# cSLIM_nRF9160.net
KiCad netlist of a schematic drawn in Altium Designer
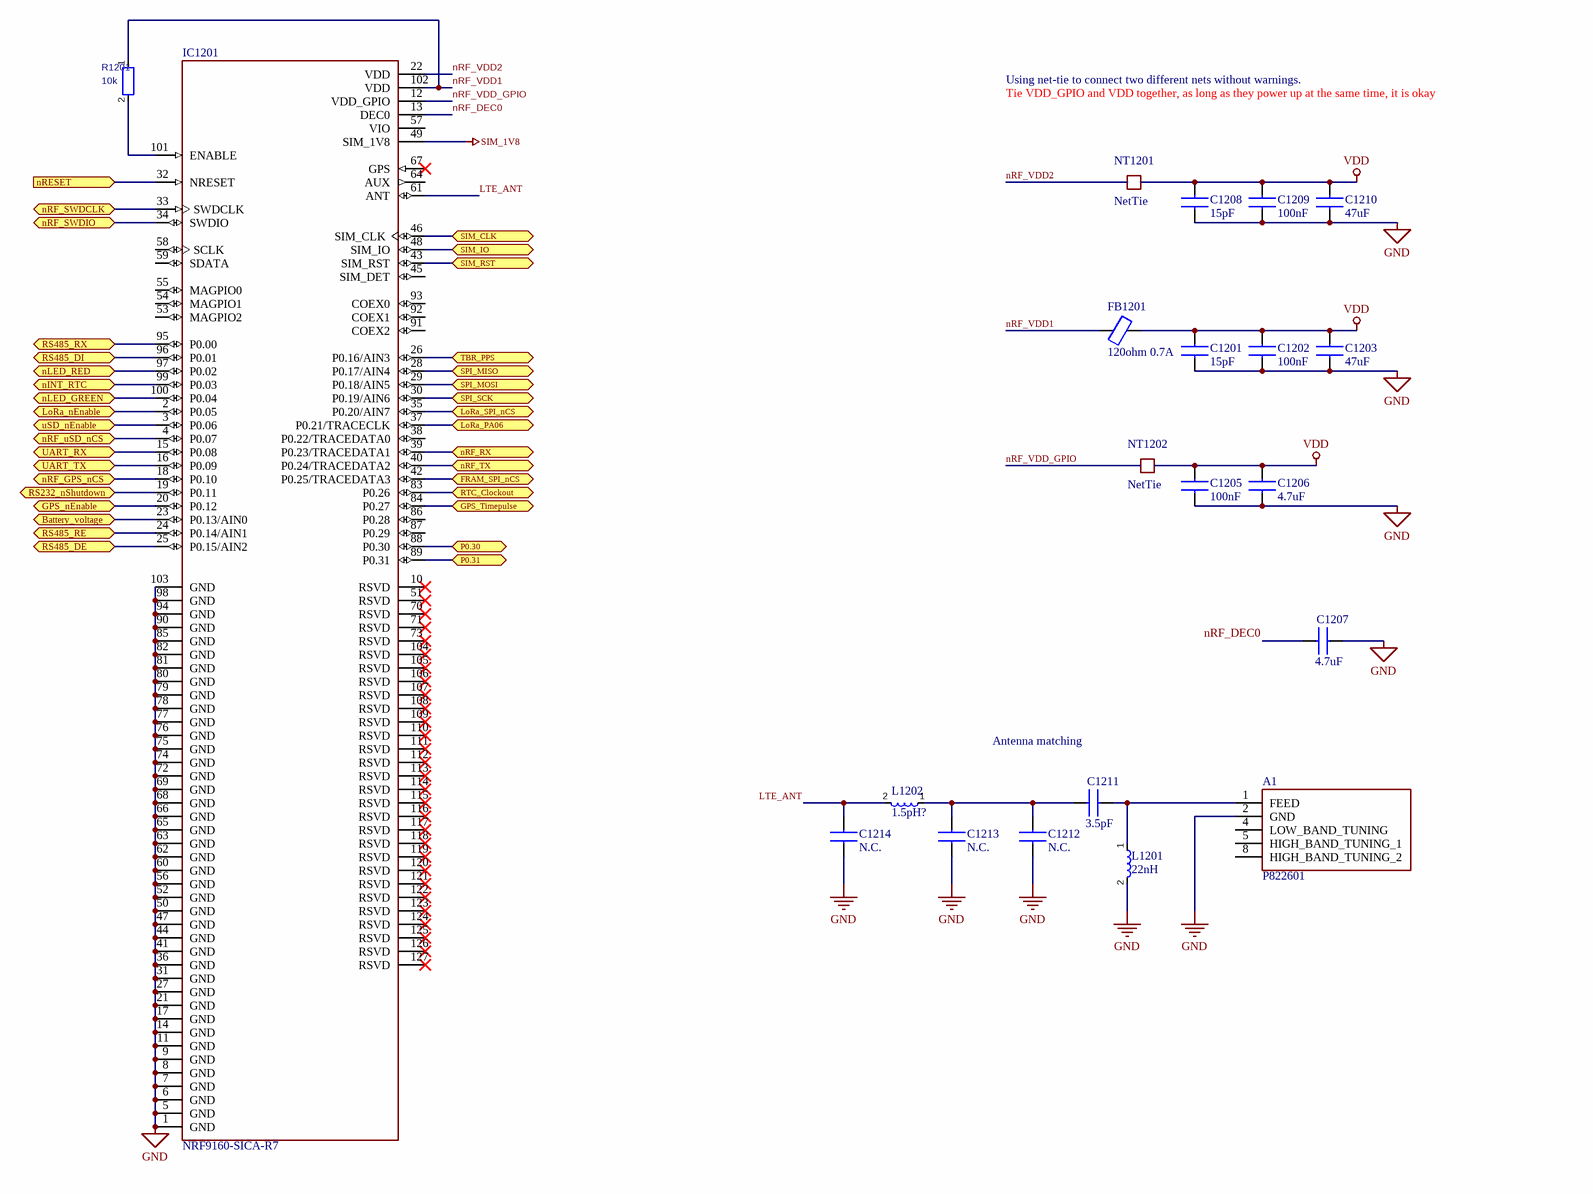
[diagram p0: cSLIM_nRF9160.SchDoc]

(export (version "E")
  (design (tool "Eeschema 10.0.6"))
  (components
    (comp (ref "A1")
      (value "P822601")
      (footprint "cSLIM-SA:P822601")
      (description "Antenna")
      (fields (field (name "MOUSER PART NUMBER") "581-P822601"))
      (libsource (lib "cSLIM-SA") (part "P822601"))
    )
    (comp (ref "C1201")
      (value "15pF")
      (footprint "cSLIM-SA:CAPC1608X90N")
      (description "Capacitor")
      (fields
        (field (name "MANUFACTURER_PART_NUMBER") "06033G104ZAT2A")
        (field (name "MOUSER PART NUMBER") "581-06033G104Z")
      )
      (libsource (lib "cSLIM-SA") (part "C"))
    )
    (comp (ref "C1202")
      (value "100nF")
      (footprint "cSLIM-SA:CAPC1608X90N")
      (description "Capacitor")
      (fields
        (field (name "MANUFACTURER_PART_NUMBER") "06033G104ZAT2A")
        (field (name "MOUSER PART NUMBER") "581-06033G104Z")
      )
      (libsource (lib "cSLIM-SA") (part "C"))
    )
    (comp (ref "C1203")
      (value "47uF")
      (footprint "cSLIM-SA:CAPC1608X90N")
      (description "Capacitor")
      (fields
        (field (name "MANUFACTURER_PART_NUMBER") "06033G104ZAT2A")
        (field (name "MOUSER PART NUMBER") "581-06033G104Z")
      )
      (libsource (lib "cSLIM-SA") (part "C"))
    )
    (comp (ref "C1205")
      (value "100nF")
      (footprint "cSLIM-SA:CAPC1608X90N")
      (description "Capacitor")
      (fields
        (field (name "MANUFACTURER_PART_NUMBER") "06033G104ZAT2A")
        (field (name "MOUSER PART NUMBER") "581-06033G104Z")
      )
      (libsource (lib "cSLIM-SA") (part "C"))
    )
    (comp (ref "C1206")
      (value "4.7uF")
      (footprint "cSLIM-SA:CAPC1608X90N")
      (description "Capacitor")
      (fields
        (field (name "MANUFACTURER_PART_NUMBER") "06033G104ZAT2A")
        (field (name "MOUSER PART NUMBER") "581-06033G104Z")
      )
      (libsource (lib "cSLIM-SA") (part "C"))
    )
    (comp (ref "C1207")
      (value "4.7uF")
      (footprint "cSLIM-SA:CAPC1608X90N")
      (description "Capacitor")
      (fields
        (field (name "MANUFACTURER_PART_NUMBER") "06033G104ZAT2A")
        (field (name "MOUSER PART NUMBER") "581-06033G104Z")
      )
      (libsource (lib "cSLIM-SA") (part "C"))
    )
    (comp (ref "C1208")
      (value "15pF")
      (footprint "cSLIM-SA:CAPC1608X90N")
      (description "Capacitor")
      (fields
        (field (name "MANUFACTURER_PART_NUMBER") "06033G104ZAT2A")
        (field (name "MOUSER PART NUMBER") "581-06033G104Z")
      )
      (libsource (lib "cSLIM-SA") (part "C"))
    )
    (comp (ref "C1209")
      (value "100nF")
      (footprint "cSLIM-SA:CAPC1608X90N")
      (description "Capacitor")
      (fields
        (field (name "MANUFACTURER_PART_NUMBER") "06033G104ZAT2A")
        (field (name "MOUSER PART NUMBER") "581-06033G104Z")
      )
      (libsource (lib "cSLIM-SA") (part "C"))
    )
    (comp (ref "C1210")
      (value "47uF")
      (footprint "cSLIM-SA:CAPC1608X90N")
      (description "Capacitor")
      (fields
        (field (name "MANUFACTURER_PART_NUMBER") "06033G104ZAT2A")
        (field (name "MOUSER PART NUMBER") "581-06033G104Z")
      )
      (libsource (lib "cSLIM-SA") (part "C"))
    )
    (comp (ref "C1211")
      (value "3.5pF")
      (footprint "cSLIM-SA:CAPC1608X90N")
      (description "Capacitor")
      (fields
        (field (name "MANUFACTURER_PART_NUMBER") "06033G104ZAT2A")
        (field (name "MOUSER PART NUMBER") "581-06033G104Z")
      )
      (libsource (lib "cSLIM-SA") (part "C"))
    )
    (comp (ref "C1212")
      (value "N.C.")
      (footprint "cSLIM-SA:CAPC1608X90N")
      (description "Capacitor")
      (fields
        (field (name "MANUFACTURER_PART_NUMBER") "06033G104ZAT2A")
        (field (name "MOUSER PART NUMBER") "581-06033G104Z")
      )
      (libsource (lib "cSLIM-SA") (part "C"))
    )
    (comp (ref "C1213")
      (value "N.C.")
      (footprint "cSLIM-SA:CAPC1608X90N")
      (description "Capacitor")
      (fields
        (field (name "MANUFACTURER_PART_NUMBER") "06033G104ZAT2A")
        (field (name "MOUSER PART NUMBER") "581-06033G104Z")
      )
      (libsource (lib "cSLIM-SA") (part "C"))
    )
    (comp (ref "C1214")
      (value "N.C.")
      (footprint "cSLIM-SA:CAPC1608X90N")
      (description "Capacitor")
      (fields
        (field (name "MANUFACTURER_PART_NUMBER") "06033G104ZAT2A")
        (field (name "MOUSER PART NUMBER") "581-06033G104Z")
      )
      (libsource (lib "cSLIM-SA") (part "C"))
    )
    (comp (ref "FB1201")
      (value "120ohm 0.7A")
      (footprint "CAPC1608X90N")
      (libsource (lib "cSLIM-SA") (part "Ferrite_Bead"))
    )
    (comp (ref "IC1201")
      (value "NRF9160-SICA-R7")
      (footprint "cSLIM-SA:XCVR_NRF9160-SICA-R7")
      (description "IC RF TxRx + MCU Cellular GPS 700MHz ~ 2.2GHz 161-TFLGA Module")
      (fields (field (name "MF") "Nordic Semiconductor ASA"))
      (libsource (lib "cSLIM-SA") (part "NRF9160-SICA-R7"))
    )
    (comp (ref "L1201") (value "22nH") (footprint "L-1608") (libsource (lib "cSLIM-SA") (part "L")))
    (comp (ref "L1202") (value "1.5pH?") (footprint "L-1608") (libsource (lib "cSLIM-SA") (part "L")))
    (comp (ref "NT1201")
      (value "NetTie")
      (footprint "NETTIE_FP")
      (libsource (lib "cSLIM-SA") (part "NetTie"))
    )
    (comp (ref "NT1202")
      (value "NetTie")
      (footprint "NETTIE_FP")
      (libsource (lib "cSLIM-SA") (part "NetTie"))
    )
    (comp (ref "R1201") (value "10k") (footprint "RESC1608X55N") (libsource (lib "cSLIM-SA") (part "R")))
  )
  (nets
    (net (code "1") (name "/Battery_voltage") (class "Default")
      (node (ref "IC1201") (pin "23") (pinfunction "P0.13/AIN0_23") (pintype "bidirectional"))
    )
    (net (code "2") (name "/FRAM_SPI_nCS") (class "Default")
      (node (ref "IC1201") (pin "42") (pinfunction "P0.25/TRACEDATA3_42") (pintype "bidirectional"))
    )
    (net (code "3") (name "/GPS_Timepulse") (class "Default")
      (node (ref "IC1201") (pin "84") (pinfunction "P0.27_84") (pintype "bidirectional"))
    )
    (net (code "4") (name "/GPS_nEnable") (class "Default")
      (node (ref "IC1201") (pin "20") (pinfunction "P0.12_20") (pintype "bidirectional"))
    )
    (net (code "5") (name "/LTE_ANT") (class "Default")
      (node (ref "C1214") (pin "1") (pinfunction "1_1") (pintype "passive"))
      (node (ref "IC1201") (pin "61") (pinfunction "ANT_61") (pintype "bidirectional"))
      (node (ref "L1202") (pin "2") (pinfunction "2_2") (pintype "passive"))
    )
    (net (code "6") (name "/LoRa_PA06") (class "Default")
      (node (ref "IC1201") (pin "37") (pinfunction "P0.21/TRACECLK_37") (pintype "bidirectional"))
    )
    (net (code "7") (name "/LoRa_SPI_nCS") (class "Default")
      (node (ref "IC1201") (pin "35") (pinfunction "P0.20/AIN7_35") (pintype "bidirectional"))
    )
    (net (code "8") (name "/LoRa_nEnable") (class "Default")
      (node (ref "IC1201") (pin "2") (pinfunction "P0.05_2") (pintype "bidirectional"))
    )
    (net (code "9") (name "/P0.30") (class "Default")
      (node (ref "IC1201") (pin "88") (pinfunction "P0.30_88") (pintype "bidirectional"))
    )
    (net (code "10") (name "/P0.31") (class "Default")
      (node (ref "IC1201") (pin "89") (pinfunction "P0.31_89") (pintype "bidirectional"))
    )
    (net (code "11") (name "/RS232_nShutdown") (class "Default")
      (node (ref "IC1201") (pin "19") (pinfunction "P0.11_19") (pintype "bidirectional"))
    )
    (net (code "12") (name "/RS485_DE") (class "Default")
      (node (ref "IC1201") (pin "25") (pinfunction "P0.15/AIN2_25") (pintype "bidirectional"))
    )
    (net (code "13") (name "/RS485_DI") (class "Default")
      (node (ref "IC1201") (pin "96") (pinfunction "P0.01_96") (pintype "bidirectional"))
    )
    (net (code "14") (name "/RS485_RE") (class "Default")
      (node (ref "IC1201") (pin "24") (pinfunction "P0.14/AIN1_24") (pintype "bidirectional"))
    )
    (net (code "15") (name "/RS485_RX") (class "Default")
      (node (ref "IC1201") (pin "95") (pinfunction "P0.00_95") (pintype "bidirectional"))
    )
    (net (code "16") (name "/RTC_Clockout") (class "Default")
      (node (ref "IC1201") (pin "83") (pinfunction "P0.26_83") (pintype "bidirectional"))
    )
    (net (code "17") (name "/SIM_CLK") (class "Default")
      (node (ref "IC1201") (pin "46") (pinfunction "SIM_CLK_46") (pintype "bidirectional"))
    )
    (net (code "18") (name "/SIM_IO") (class "Default")
      (node (ref "IC1201") (pin "48") (pinfunction "SIM_IO_48") (pintype "bidirectional"))
    )
    (net (code "19") (name "/SIM_RST") (class "Default")
      (node (ref "IC1201") (pin "43") (pinfunction "SIM_RST_43") (pintype "bidirectional"))
    )
    (net (code "20") (name "/SPI_MISO") (class "Default")
      (node (ref "IC1201") (pin "28") (pinfunction "P0.17/AIN4_28") (pintype "bidirectional"))
    )
    (net (code "21") (name "/SPI_MOSI") (class "Default")
      (node (ref "IC1201") (pin "29") (pinfunction "P0.18/AIN5_29") (pintype "bidirectional"))
    )
    (net (code "22") (name "/SPI_SCK") (class "Default")
      (node (ref "IC1201") (pin "30") (pinfunction "P0.19/AIN6_30") (pintype "bidirectional"))
    )
    (net (code "23") (name "/TBR_PPS") (class "Default")
      (node (ref "IC1201") (pin "26") (pinfunction "P0.16/AIN3_26") (pintype "bidirectional"))
    )
    (net (code "24") (name "/UART_RX") (class "Default")
      (node (ref "IC1201") (pin "15") (pinfunction "P0.08_15") (pintype "bidirectional"))
    )
    (net (code "25") (name "/UART_TX") (class "Default")
      (node (ref "IC1201") (pin "16") (pinfunction "P0.09_16") (pintype "bidirectional"))
    )
    (net (code "26") (name "/nINT_RTC") (class "Default")
      (node (ref "IC1201") (pin "99") (pinfunction "P0.03_99") (pintype "bidirectional"))
    )
    (net (code "27") (name "/nLED_GREEN") (class "Default")
      (node (ref "IC1201") (pin "100") (pinfunction "P0.04_100") (pintype "bidirectional"))
    )
    (net (code "28") (name "/nLED_RED") (class "Default")
      (node (ref "IC1201") (pin "97") (pinfunction "P0.02_97") (pintype "bidirectional"))
    )
    (net (code "29") (name "/nRESET") (class "Default")
      (node (ref "IC1201") (pin "32") (pinfunction "NRESET_32") (pintype "input"))
    )
    (net (code "30") (name "/nRF_DEC0") (class "Default")
      (node (ref "C1207") (pin "1") (pinfunction "1_1") (pintype "passive"))
      (node (ref "IC1201") (pin "13") (pinfunction "DEC0_13") (pintype "power_in"))
    )
    (net (code "31") (name "/nRF_GPS_nCS") (class "Default")
      (node (ref "IC1201") (pin "18") (pinfunction "P0.10_18") (pintype "bidirectional"))
    )
    (net (code "32") (name "/nRF_RX") (class "Default")
      (node (ref "IC1201") (pin "39") (pinfunction "P0.23/TRACEDATA1_39") (pintype "bidirectional"))
    )
    (net (code "33") (name "/nRF_SWDCLK") (class "Default")
      (node (ref "IC1201") (pin "33") (pinfunction "SWDCLK_33") (pintype "input"))
    )
    (net (code "34") (name "/nRF_SWDIO") (class "Default")
      (node (ref "IC1201") (pin "34") (pinfunction "SWDIO_34") (pintype "bidirectional"))
    )
    (net (code "35") (name "/nRF_TX") (class "Default")
      (node (ref "IC1201") (pin "40") (pinfunction "P0.24/TRACEDATA2_40") (pintype "bidirectional"))
    )
    (net (code "36") (name "/nRF_VDD1") (class "Default")
      (node (ref "FB1201") (pin "1") (pinfunction "1_1") (pintype "passive"))
      (node (ref "IC1201") (pin "102") (pinfunction "VDD_102") (pintype "power_in"))
      (node (ref "R1201") (pin "1") (pinfunction "1_1") (pintype "passive"))
    )
    (net (code "37") (name "/nRF_VDD2") (class "Default")
      (node (ref "IC1201") (pin "22") (pinfunction "VDD_22") (pintype "power_in"))
      (node (ref "NT1201") (pin "1") (pintype "passive"))
    )
    (net (code "38") (name "/nRF_VDD_GPIO") (class "Default")
      (node (ref "IC1201") (pin "12") (pinfunction "VDD_GPIO_12") (pintype "power_in"))
      (node (ref "NT1202") (pin "1") (pintype "passive"))
    )
    (net (code "39") (name "/nRF_uSD_nCS") (class "Default")
      (node (ref "IC1201") (pin "4") (pinfunction "P0.07_4") (pintype "bidirectional"))
    )
    (net (code "40") (name "/uSD_nEnable") (class "Default")
      (node (ref "IC1201") (pin "3") (pinfunction "P0.06_3") (pintype "bidirectional"))
    )
    (net (code "41") (name "GND") (class "Default")
      (node (ref "A1") (pin "2") (pinfunction "GND_2") (pintype "passive"))
      (node (ref "C1201") (pin "2") (pinfunction "2_2") (pintype "passive"))
      (node (ref "C1202") (pin "2") (pinfunction "2_2") (pintype "passive"))
      (node (ref "C1203") (pin "2") (pinfunction "2_2") (pintype "passive"))
      (node (ref "C1205") (pin "2") (pinfunction "2_2") (pintype "passive"))
      (node (ref "C1206") (pin "2") (pinfunction "2_2") (pintype "passive"))
      (node (ref "C1207") (pin "2") (pinfunction "2_2") (pintype "passive"))
      (node (ref "C1208") (pin "2") (pinfunction "2_2") (pintype "passive"))
      (node (ref "C1209") (pin "2") (pinfunction "2_2") (pintype "passive"))
      (node (ref "C1210") (pin "2") (pinfunction "2_2") (pintype "passive"))
      (node (ref "C1212") (pin "2") (pinfunction "2_2") (pintype "passive"))
      (node (ref "C1213") (pin "2") (pinfunction "2_2") (pintype "passive"))
      (node (ref "C1214") (pin "2") (pinfunction "2_2") (pintype "passive"))
      (node (ref "IC1201") (pin "1") (pinfunction "GND_1") (pintype "power_in"))
      (node (ref "IC1201") (pin "103") (pinfunction "GND_103") (pintype "power_in"))
      (node (ref "IC1201") (pin "11") (pinfunction "GND_11") (pintype "passive"))
      (node (ref "IC1201") (pin "14") (pinfunction "GND_14") (pintype "power_in"))
      (node (ref "IC1201") (pin "17") (pinfunction "GND_17") (pintype "power_in"))
      (node (ref "IC1201") (pin "21") (pinfunction "GND_21") (pintype "power_in"))
      (node (ref "IC1201") (pin "27") (pinfunction "GND_27") (pintype "power_in"))
      (node (ref "IC1201") (pin "31") (pinfunction "GND_31") (pintype "power_in"))
      (node (ref "IC1201") (pin "36") (pinfunction "GND_36") (pintype "power_in"))
      (node (ref "IC1201") (pin "41") (pinfunction "GND_41") (pintype "power_in"))
      (node (ref "IC1201") (pin "44") (pinfunction "GND_44") (pintype "power_in"))
      (node (ref "IC1201") (pin "47") (pinfunction "GND_47") (pintype "power_in"))
      (node (ref "IC1201") (pin "5") (pinfunction "GND_5") (pintype "power_in"))
      (node (ref "IC1201") (pin "50") (pinfunction "GND_50") (pintype "power_in"))
      (node (ref "IC1201") (pin "52") (pinfunction "GND_52") (pintype "power_in"))
      (node (ref "IC1201") (pin "56") (pinfunction "GND_56") (pintype "power_in"))
      (node (ref "IC1201") (pin "6") (pinfunction "GND_6") (pintype "passive"))
      (node (ref "IC1201") (pin "60") (pinfunction "GND_60") (pintype "power_in"))
      (node (ref "IC1201") (pin "62") (pinfunction "GND_62") (pintype "power_in"))
      (node (ref "IC1201") (pin "63") (pinfunction "GND_63") (pintype "power_in"))
      (node (ref "IC1201") (pin "65") (pinfunction "GND_65") (pintype "power_in"))
      (node (ref "IC1201") (pin "66") (pinfunction "GND_66") (pintype "power_in"))
      (node (ref "IC1201") (pin "68") (pinfunction "GND_68") (pintype "passive"))
      (node (ref "IC1201") (pin "69") (pinfunction "GND_69") (pintype "passive"))
      (node (ref "IC1201") (pin "7") (pinfunction "GND_7") (pintype "passive"))
      (node (ref "IC1201") (pin "72") (pinfunction "GND_72") (pintype "power_in"))
      (node (ref "IC1201") (pin "74") (pinfunction "GND_74") (pintype "power_in"))
      (node (ref "IC1201") (pin "75") (pinfunction "GND_75") (pintype "power_in"))
      (node (ref "IC1201") (pin "76") (pinfunction "GND_76") (pintype "power_in"))
      (node (ref "IC1201") (pin "77") (pinfunction "GND_77") (pintype "power_in"))
      (node (ref "IC1201") (pin "78") (pinfunction "GND_78") (pintype "power_in"))
      (node (ref "IC1201") (pin "79") (pinfunction "GND_79") (pintype "power_in"))
      (node (ref "IC1201") (pin "8") (pinfunction "GND_8") (pintype "passive"))
      (node (ref "IC1201") (pin "80") (pinfunction "GND_80") (pintype "power_in"))
      (node (ref "IC1201") (pin "81") (pinfunction "GND_81") (pintype "power_in"))
      (node (ref "IC1201") (pin "82") (pinfunction "GND_82") (pintype "power_in"))
      (node (ref "IC1201") (pin "85") (pinfunction "GND_85") (pintype "power_in"))
      (node (ref "IC1201") (pin "9") (pinfunction "GND_9") (pintype "power_in"))
      (node (ref "IC1201") (pin "90") (pinfunction "GND_90") (pintype "power_in"))
      (node (ref "IC1201") (pin "94") (pinfunction "GND_94") (pintype "power_in"))
      (node (ref "IC1201") (pin "98") (pinfunction "GND_98") (pintype "power_in"))
      (node (ref "L1201") (pin "2") (pinfunction "2_2") (pintype "passive"))
    )
    (net (code "42") (name "Net-(A1-FEED)") (class "Default")
      (node (ref "A1") (pin "1") (pinfunction "FEED_1") (pintype "passive"))
      (node (ref "C1211") (pin "2") (pinfunction "2_2") (pintype "passive"))
      (node (ref "L1201") (pin "1") (pinfunction "1_1") (pintype "passive"))
    )
    (net (code "43") (name "Net-(C1211-Pad1)") (class "Default")
      (node (ref "C1211") (pin "1") (pinfunction "1_1") (pintype "passive"))
      (node (ref "C1212") (pin "1") (pinfunction "1_1") (pintype "passive"))
      (node (ref "C1213") (pin "1") (pinfunction "1_1") (pintype "passive"))
      (node (ref "L1202") (pin "1") (pinfunction "1_1") (pintype "passive"))
    )
    (net (code "44") (name "Net-(IC1201-ENABLE)") (class "Default")
      (node (ref "IC1201") (pin "101") (pinfunction "ENABLE_101") (pintype "input"))
      (node (ref "R1201") (pin "2") (pinfunction "2_2") (pintype "passive"))
    )
    (net (code "45") (name "SIM_1V8") (class "Default")
      (node (ref "IC1201") (pin "49") (pinfunction "SIM_1V8_49") (pintype "power_in"))
    )
    (net (code "46") (name "VDD") (class "Default")
      (node (ref "C1201") (pin "1") (pinfunction "1_1") (pintype "passive"))
      (node (ref "C1202") (pin "1") (pinfunction "1_1") (pintype "passive"))
      (node (ref "C1203") (pin "1") (pinfunction "1_1") (pintype "passive"))
      (node (ref "C1205") (pin "1") (pinfunction "1_1") (pintype "passive"))
      (node (ref "C1206") (pin "1") (pinfunction "1_1") (pintype "passive"))
      (node (ref "C1208") (pin "1") (pinfunction "1_1") (pintype "passive"))
      (node (ref "C1209") (pin "1") (pinfunction "1_1") (pintype "passive"))
      (node (ref "C1210") (pin "1") (pinfunction "1_1") (pintype "passive"))
      (node (ref "FB1201") (pin "2") (pinfunction "2_2") (pintype "passive"))
      (node (ref "NT1201") (pin "2") (pintype "passive"))
      (node (ref "NT1202") (pin "2") (pintype "passive"))
    )
    (net (code "47") (name "unconnected-(A1-HIGH_BAND_TUNING_1-Pad5)") (class "Default")
      (node (ref "A1") (pin "5") (pinfunction "HIGH_BAND_TUNING_1_5") (pintype "passive"))
    )
    (net (code "48") (name "unconnected-(A1-HIGH_BAND_TUNING_2-Pad8)") (class "Default")
      (node (ref "A1") (pin "8") (pinfunction "HIGH_BAND_TUNING_2_8") (pintype "passive"))
    )
    (net (code "49") (name "unconnected-(A1-LOW_BAND_TUNING-Pad4)") (class "Default")
      (node (ref "A1") (pin "4") (pinfunction "LOW_BAND_TUNING_4") (pintype "passive"))
    )
    (net (code "50") (name "unconnected-(IC1201-AUX-Pad64)") (class "Default")
      (node (ref "IC1201") (pin "64") (pinfunction "AUX_64") (pintype "output"))
    )
    (net (code "51") (name "unconnected-(IC1201-COEX0-Pad93)") (class "Default")
      (node (ref "IC1201") (pin "93") (pinfunction "COEX0_93") (pintype "bidirectional"))
    )
    (net (code "52") (name "unconnected-(IC1201-COEX1-Pad92)") (class "Default")
      (node (ref "IC1201") (pin "92") (pinfunction "COEX1_92") (pintype "bidirectional"))
    )
    (net (code "53") (name "unconnected-(IC1201-COEX2-Pad91)") (class "Default")
      (node (ref "IC1201") (pin "91") (pinfunction "COEX2_91") (pintype "bidirectional"))
    )
    (net (code "54") (name "unconnected-(IC1201-GPS-Pad67)") (class "Default")
      (node (ref "IC1201") (pin "67") (pinfunction "GPS_67") (pintype "input+no_connect"))
    )
    (net (code "55") (name "unconnected-(IC1201-MAGPIO0-Pad55)") (class "Default")
      (node (ref "IC1201") (pin "55") (pinfunction "MAGPIO0_55") (pintype "bidirectional"))
    )
    (net (code "56") (name "unconnected-(IC1201-MAGPIO1-Pad54)") (class "Default")
      (node (ref "IC1201") (pin "54") (pinfunction "MAGPIO1_54") (pintype "bidirectional"))
    )
    (net (code "57") (name "unconnected-(IC1201-MAGPIO2-Pad53)") (class "Default")
      (node (ref "IC1201") (pin "53") (pinfunction "MAGPIO2_53") (pintype "bidirectional"))
    )
    (net (code "58") (name "unconnected-(IC1201-P0.22{slash}TRACEDATA0-Pad38)") (class "Default")
      (node (ref "IC1201") (pin "38") (pinfunction "P0.22/TRACEDATA0_38") (pintype "bidirectional"))
    )
    (net (code "59") (name "unconnected-(IC1201-P0.28-Pad86)") (class "Default")
      (node (ref "IC1201") (pin "86") (pinfunction "P0.28_86") (pintype "bidirectional"))
    )
    (net (code "60") (name "unconnected-(IC1201-P0.29-Pad87)") (class "Default")
      (node (ref "IC1201") (pin "87") (pinfunction "P0.29_87") (pintype "bidirectional"))
    )
    (net (code "61") (name "unconnected-(IC1201-RSVD-Pad10)") (class "Default")
      (node (ref "IC1201") (pin "10") (pinfunction "RSVD_10") (pintype "passive+no_connect"))
    )
    (net (code "62") (name "unconnected-(IC1201-RSVD-Pad51)") (class "Default")
      (node (ref "IC1201") (pin "51") (pinfunction "RSVD_51") (pintype "passive+no_connect"))
    )
    (net (code "63") (name "unconnected-(IC1201-RSVD-Pad70)") (class "Default")
      (node (ref "IC1201") (pin "70") (pinfunction "RSVD_70") (pintype "passive+no_connect"))
    )
    (net (code "64") (name "unconnected-(IC1201-RSVD-Pad71)") (class "Default")
      (node (ref "IC1201") (pin "71") (pinfunction "RSVD_71") (pintype "passive+no_connect"))
    )
    (net (code "65") (name "unconnected-(IC1201-RSVD-Pad73)") (class "Default")
      (node (ref "IC1201") (pin "73") (pinfunction "RSVD_73") (pintype "passive+no_connect"))
    )
    (net (code "66") (name "unconnected-(IC1201-RSVD-Pad104)") (class "Default")
      (node (ref "IC1201") (pin "104") (pinfunction "RSVD_104") (pintype "passive+no_connect"))
    )
    (net (code "67") (name "unconnected-(IC1201-RSVD-Pad105)") (class "Default")
      (node (ref "IC1201") (pin "105") (pinfunction "RSVD_105") (pintype "passive+no_connect"))
    )
    (net (code "68") (name "unconnected-(IC1201-RSVD-Pad106)") (class "Default")
      (node (ref "IC1201") (pin "106") (pinfunction "RSVD_106") (pintype "passive+no_connect"))
    )
    (net (code "69") (name "unconnected-(IC1201-RSVD-Pad107)") (class "Default")
      (node (ref "IC1201") (pin "107") (pinfunction "RSVD_107") (pintype "passive+no_connect"))
    )
    (net (code "70") (name "unconnected-(IC1201-RSVD-Pad108)") (class "Default")
      (node (ref "IC1201") (pin "108") (pinfunction "RSVD_108") (pintype "passive+no_connect"))
    )
    (net (code "71") (name "unconnected-(IC1201-RSVD-Pad109)") (class "Default")
      (node (ref "IC1201") (pin "109") (pinfunction "RSVD_109") (pintype "passive+no_connect"))
    )
    (net (code "72") (name "unconnected-(IC1201-RSVD-Pad110)") (class "Default")
      (node (ref "IC1201") (pin "110") (pinfunction "RSVD_110") (pintype "passive+no_connect"))
    )
    (net (code "73") (name "unconnected-(IC1201-RSVD-Pad111)") (class "Default")
      (node (ref "IC1201") (pin "111") (pinfunction "RSVD_111") (pintype "passive+no_connect"))
    )
    (net (code "74") (name "unconnected-(IC1201-RSVD-Pad112)") (class "Default")
      (node (ref "IC1201") (pin "112") (pinfunction "RSVD_112") (pintype "passive+no_connect"))
    )
    (net (code "75") (name "unconnected-(IC1201-RSVD-Pad113)") (class "Default")
      (node (ref "IC1201") (pin "113") (pinfunction "RSVD_113") (pintype "passive+no_connect"))
    )
    (net (code "76") (name "unconnected-(IC1201-RSVD-Pad114)") (class "Default")
      (node (ref "IC1201") (pin "114") (pinfunction "RSVD_114") (pintype "passive+no_connect"))
    )
    (net (code "77") (name "unconnected-(IC1201-RSVD-Pad115)") (class "Default")
      (node (ref "IC1201") (pin "115") (pinfunction "RSVD_115") (pintype "passive+no_connect"))
    )
    (net (code "78") (name "unconnected-(IC1201-RSVD-Pad116)") (class "Default")
      (node (ref "IC1201") (pin "116") (pinfunction "RSVD_116") (pintype "passive+no_connect"))
    )
    (net (code "79") (name "unconnected-(IC1201-RSVD-Pad117)") (class "Default")
      (node (ref "IC1201") (pin "117") (pinfunction "RSVD_117") (pintype "passive+no_connect"))
    )
    (net (code "80") (name "unconnected-(IC1201-RSVD-Pad118)") (class "Default")
      (node (ref "IC1201") (pin "118") (pinfunction "RSVD_118") (pintype "passive+no_connect"))
    )
    (net (code "81") (name "unconnected-(IC1201-RSVD-Pad119)") (class "Default")
      (node (ref "IC1201") (pin "119") (pinfunction "RSVD_119") (pintype "passive+no_connect"))
    )
    (net (code "82") (name "unconnected-(IC1201-RSVD-Pad120)") (class "Default")
      (node (ref "IC1201") (pin "120") (pinfunction "RSVD_120") (pintype "passive+no_connect"))
    )
    (net (code "83") (name "unconnected-(IC1201-RSVD-Pad121)") (class "Default")
      (node (ref "IC1201") (pin "121") (pinfunction "RSVD_121") (pintype "passive+no_connect"))
    )
    (net (code "84") (name "unconnected-(IC1201-RSVD-Pad122)") (class "Default")
      (node (ref "IC1201") (pin "122") (pinfunction "RSVD_122") (pintype "passive+no_connect"))
    )
    (net (code "85") (name "unconnected-(IC1201-RSVD-Pad123)") (class "Default")
      (node (ref "IC1201") (pin "123") (pinfunction "RSVD_123") (pintype "passive+no_connect"))
    )
    (net (code "86") (name "unconnected-(IC1201-RSVD-Pad124)") (class "Default")
      (node (ref "IC1201") (pin "124") (pinfunction "RSVD_124") (pintype "passive+no_connect"))
    )
    (net (code "87") (name "unconnected-(IC1201-RSVD-Pad125)") (class "Default")
      (node (ref "IC1201") (pin "125") (pinfunction "RSVD_125") (pintype "passive+no_connect"))
    )
    (net (code "88") (name "unconnected-(IC1201-RSVD-Pad126)") (class "Default")
      (node (ref "IC1201") (pin "126") (pinfunction "RSVD_126") (pintype "passive+no_connect"))
    )
    (net (code "89") (name "unconnected-(IC1201-RSVD-Pad127)") (class "Default")
      (node (ref "IC1201") (pin "127") (pinfunction "RSVD_127") (pintype "passive+no_connect"))
    )
    (net (code "90") (name "unconnected-(IC1201-SCLK-Pad58)") (class "Default")
      (node (ref "IC1201") (pin "58") (pinfunction "SCLK_58") (pintype "bidirectional"))
    )
    (net (code "91") (name "unconnected-(IC1201-SDATA-Pad59)") (class "Default")
      (node (ref "IC1201") (pin "59") (pinfunction "SDATA_59") (pintype "bidirectional"))
    )
    (net (code "92") (name "unconnected-(IC1201-SIM_DET-Pad45)") (class "Default")
      (node (ref "IC1201") (pin "45") (pinfunction "SIM_DET_45") (pintype "bidirectional"))
    )
    (net (code "93") (name "unconnected-(IC1201-VIO-Pad57)") (class "Default")
      (node (ref "IC1201") (pin "57") (pinfunction "VIO_57") (pintype "power_in"))
    )
  )
)
